# Knock_Sensing.net
KiCad netlist of a schematic drawn in Altium Designer
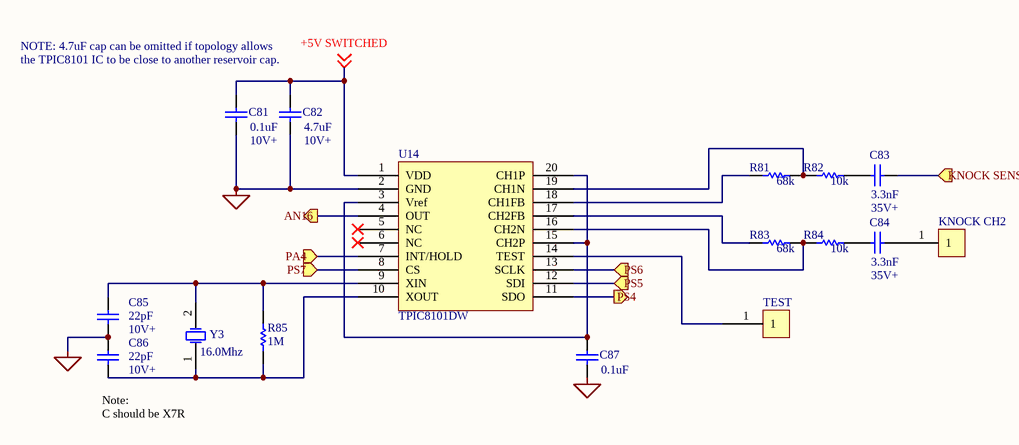
[diagram p0: Knock Sensing.SchDoc]

(export (version "E")
  (design (tool "Eeschema 10.0.6"))
  (components
    (comp (ref "C81")
      (value "0.1uF")
      (footprint "RAD-0.3")
      (description "Capacitor")
      (fields (field (name "PUBLISHER") "Altium Limited"))
      (libsource (lib "Miscellaneous Devices") (part "Cap"))
    )
    (comp (ref "C82")
      (value "4.7uF")
      (footprint "RAD-0.3")
      (description "Capacitor")
      (fields (field (name "PUBLISHER") "Altium Limited"))
      (libsource (lib "Miscellaneous Devices") (part "Cap"))
    )
    (comp (ref "C83")
      (value "3.3nF")
      (footprint "RAD-0.3")
      (description "Capacitor")
      (fields (field (name "PUBLISHER") "Altium Limited"))
      (libsource (lib "Miscellaneous Devices") (part "Cap"))
    )
    (comp (ref "C84")
      (value "3.3nF")
      (footprint "RAD-0.3")
      (description "Capacitor")
      (fields (field (name "PUBLISHER") "Altium Limited"))
      (libsource (lib "Miscellaneous Devices") (part "Cap"))
    )
    (comp (ref "C85")
      (value "22pF")
      (footprint "RAD-0.3")
      (description "Capacitor")
      (fields (field (name "PUBLISHER") "Altium Limited"))
      (libsource (lib "Miscellaneous Devices") (part "Cap"))
    )
    (comp (ref "C86")
      (value "22pF")
      (footprint "RAD-0.3")
      (description "Capacitor")
      (fields (field (name "PUBLISHER") "Altium Limited"))
      (libsource (lib "Miscellaneous Devices") (part "Cap"))
    )
    (comp (ref "C87")
      (value "0.1uF")
      (footprint "RAD-0.3")
      (description "Capacitor")
      (fields (field (name "PUBLISHER") "Altium Limited"))
      (libsource (lib "Miscellaneous Devices") (part "Cap"))
    )
    (comp (ref "KNOCK CH2") (value "~") (libsource (lib "FreeEMS Schematic Library") (part "HEADER 1")))
    (comp (ref "R81")
      (value "68k")
      (footprint "AXIAL-0.3")
      (description "Resistor")
      (fields (field (name "PUBLISHER") "Altium Limited"))
      (libsource (lib "Miscellaneous Devices") (part "Res1"))
    )
    (comp (ref "R82")
      (value "10k")
      (footprint "AXIAL-0.3")
      (description "Resistor")
      (fields (field (name "PUBLISHER") "Altium Limited"))
      (libsource (lib "Miscellaneous Devices") (part "Res1"))
    )
    (comp (ref "R83")
      (value "68k")
      (footprint "AXIAL-0.3")
      (description "Resistor")
      (fields (field (name "PUBLISHER") "Altium Limited"))
      (libsource (lib "Miscellaneous Devices") (part "Res1"))
    )
    (comp (ref "R84")
      (value "10k")
      (footprint "AXIAL-0.3")
      (description "Resistor")
      (fields (field (name "PUBLISHER") "Altium Limited"))
      (libsource (lib "Miscellaneous Devices") (part "Res1"))
    )
    (comp (ref "R85")
      (value "1M")
      (footprint "AXIAL-0.3")
      (description "Resistor")
      (fields (field (name "PUBLISHER") "Altium Limited"))
      (libsource (lib "Miscellaneous Devices") (part "Res1"))
    )
    (comp (ref "TEST") (value "~") (libsource (lib "FreeEMS Schematic Library") (part "HEADER 1")))
    (comp (ref "U14")
      (value "TPIC8101DW")
      (footprint "SOIC20_N")
      (libsource (lib "FreeEMS Schematic Library") (part "TPIC8101DW"))
    )
    (comp (ref "Y3")
      (value "16.0Mhz")
      (footprint "R38")
      (description "Crystal Oscillator")
      (fields (field (name "PUBLISHER") "Altium Limited"))
      (libsource (lib "Miscellaneous Devices") (part "XTAL"))
    )
  )
  (nets
    (net (code "1") (name "+5V SWITCHED") (class "Default")
      (node (ref "C81") (pin "2") (pinfunction "2_2") (pintype "passive"))
      (node (ref "C82") (pin "2") (pinfunction "2_2") (pintype "passive"))
      (node (ref "U14") (pin "1") (pinfunction "VDD_1") (pintype "passive"))
    )
    (net (code "2") (name "/AN16") (class "Default")
      (node (ref "U14") (pin "4") (pinfunction "OUT_4") (pintype "passive"))
    )
    (net (code "3") (name "/KNOCK SENSOR") (class "Default")
      (node (ref "C83") (pin "2") (pinfunction "2_2") (pintype "passive"))
    )
    (net (code "4") (name "/PA4") (class "Default")
      (node (ref "U14") (pin "7") (pinfunction "INT/HOLD_7") (pintype "passive"))
    )
    (net (code "5") (name "/PS4") (class "Default")
      (node (ref "U14") (pin "11") (pinfunction "SDO_11") (pintype "passive"))
    )
    (net (code "6") (name "/PS5") (class "Default")
      (node (ref "U14") (pin "12") (pinfunction "SDI_12") (pintype "passive"))
    )
    (net (code "7") (name "/PS6") (class "Default")
      (node (ref "U14") (pin "13") (pinfunction "SCLK_13") (pintype "passive"))
    )
    (net (code "8") (name "/PS7") (class "Default")
      (node (ref "U14") (pin "8") (pinfunction "CS_8") (pintype "passive"))
    )
    (net (code "9") (name "<NO NET>") (class "Default")
      (node (ref "C81") (pin "1") (pinfunction "1_1") (pintype "passive"))
      (node (ref "C82") (pin "1") (pinfunction "1_1") (pintype "passive"))
      (node (ref "C85") (pin "1") (pinfunction "1_1") (pintype "passive"))
      (node (ref "C86") (pin "2") (pinfunction "2_2") (pintype "passive"))
      (node (ref "C87") (pin "1") (pinfunction "1_1") (pintype "passive"))
      (node (ref "U14") (pin "2") (pinfunction "GND_2") (pintype "passive"))
    )
    (net (code "10") (name "Net-(C83-Pad1)") (class "Default")
      (node (ref "C83") (pin "1") (pinfunction "1_1") (pintype "passive"))
      (node (ref "R82") (pin "2") (pinfunction "2_2") (pintype "passive"))
    )
    (net (code "11") (name "Net-(C84-Pad1)") (class "Default")
      (node (ref "C84") (pin "1") (pinfunction "1_1") (pintype "passive"))
      (node (ref "R84") (pin "2") (pinfunction "2_2") (pintype "passive"))
    )
    (net (code "12") (name "Net-(C84-Pad2)") (class "Default")
      (node (ref "C84") (pin "2") (pinfunction "2_2") (pintype "passive"))
      (node (ref "KNOCK CH2") (pin "1") (pinfunction "1_1") (pintype "passive"))
    )
    (net (code "13") (name "Net-(U14-CH1FB)") (class "Default")
      (node (ref "R81") (pin "1") (pinfunction "1_1") (pintype "passive"))
      (node (ref "U14") (pin "18") (pinfunction "CH1FB_18") (pintype "passive"))
    )
    (net (code "14") (name "Net-(U14-CH1N)") (class "Default")
      (node (ref "R81") (pin "2") (pinfunction "2_2") (pintype "passive"))
      (node (ref "R82") (pin "1") (pinfunction "1_1") (pintype "passive"))
      (node (ref "U14") (pin "19") (pinfunction "CH1N_19") (pintype "passive"))
    )
    (net (code "15") (name "Net-(U14-CH1P)") (class "Default")
      (node (ref "C87") (pin "2") (pinfunction "2_2") (pintype "passive"))
      (node (ref "U14") (pin "15") (pinfunction "CH2P_15") (pintype "passive"))
      (node (ref "U14") (pin "20") (pinfunction "CH1P_20") (pintype "passive"))
      (node (ref "U14") (pin "3") (pinfunction "Vref_3") (pintype "passive"))
    )
    (net (code "16") (name "Net-(U14-CH2FB)") (class "Default")
      (node (ref "R83") (pin "1") (pinfunction "1_1") (pintype "passive"))
      (node (ref "U14") (pin "17") (pinfunction "CH2FB_17") (pintype "passive"))
    )
    (net (code "17") (name "Net-(U14-CH2N)") (class "Default")
      (node (ref "R83") (pin "2") (pinfunction "2_2") (pintype "passive"))
      (node (ref "R84") (pin "1") (pinfunction "1_1") (pintype "passive"))
      (node (ref "U14") (pin "16") (pinfunction "CH2N_16") (pintype "passive"))
    )
    (net (code "18") (name "Net-(U14-TEST)") (class "Default")
      (node (ref "TEST") (pin "1") (pinfunction "1_1") (pintype "passive"))
      (node (ref "U14") (pin "14") (pinfunction "TEST_14") (pintype "passive"))
    )
    (net (code "19") (name "Net-(U14-XIN)") (class "Default")
      (node (ref "C85") (pin "2") (pinfunction "2_2") (pintype "passive"))
      (node (ref "R85") (pin "1") (pinfunction "1_1") (pintype "passive"))
      (node (ref "U14") (pin "9") (pinfunction "XIN_9") (pintype "passive"))
      (node (ref "Y3") (pin "2") (pinfunction "OSC2_2") (pintype "passive"))
    )
    (net (code "20") (name "Net-(U14-XOUT)") (class "Default")
      (node (ref "C86") (pin "1") (pinfunction "1_1") (pintype "passive"))
      (node (ref "R85") (pin "2") (pinfunction "2_2") (pintype "passive"))
      (node (ref "U14") (pin "10") (pinfunction "XOUT_10") (pintype "passive"))
      (node (ref "Y3") (pin "1") (pinfunction "OSC1_1") (pintype "passive"))
    )
    (net (code "21") (name "unconnected-(U14-NC-Pad5)") (class "Default")
      (node (ref "U14") (pin "5") (pinfunction "NC_5") (pintype "passive+no_connect"))
    )
    (net (code "22") (name "unconnected-(U14-NC-Pad6)") (class "Default")
      (node (ref "U14") (pin "6") (pinfunction "NC_6") (pintype "passive+no_connect"))
    )
  )
)
